# IOTM222.net
KiCad netlist of a schematic drawn in Altium Designer
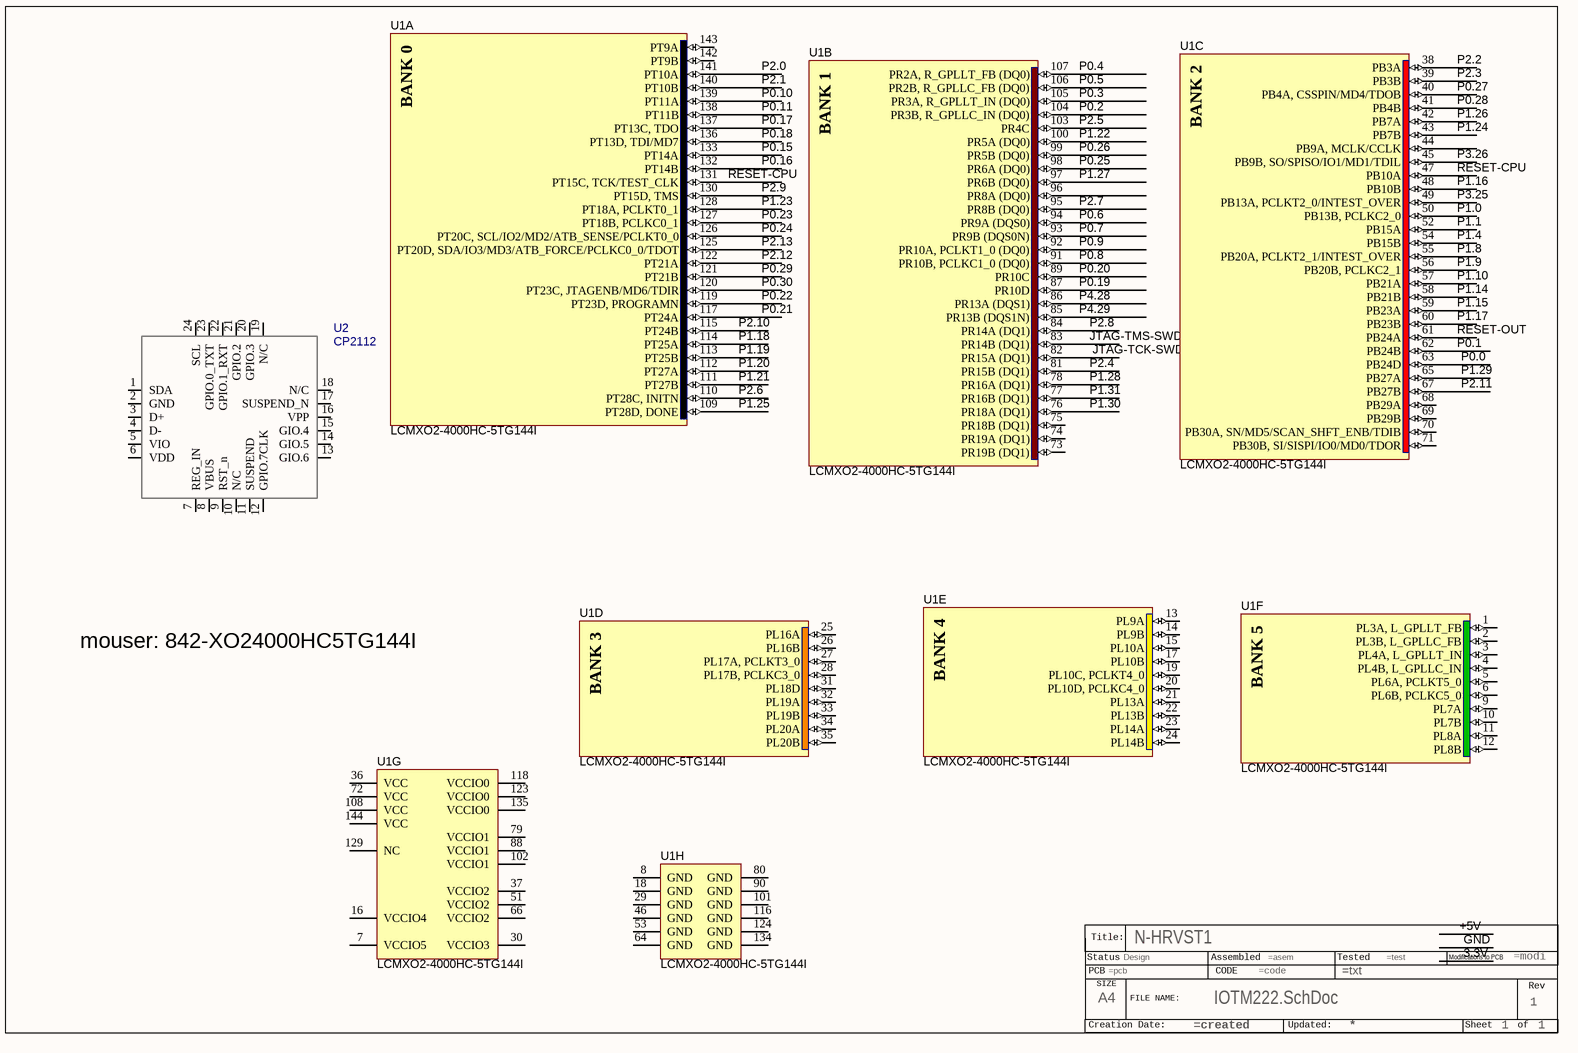
[diagram p0: IOTM222.SchDoc]

(export (version "E")
  (design (tool "Eeschema 10.0.6"))
  (components
    (comp (ref "?*")
      (value "TITLEBLOCK2")
      (fields (field (name "PAGE NUMPER") "1") (field (name "PAGE COUNT") "1"))
      (libsource (lib "NX2") (part "TITLEBLOCK2"))
    )
    (comp (ref "U1")
      (value "LCMXO2-4000HC-5TG144I")
      (footprint "TQFP144_N")
      (libsource (lib "MachXO2") (part "LCMXO2-4000HC-5TG144I"))
    )
    (comp (ref "U2") (value "CP2112") (footprint "QFN24") (libsource (lib "NX1") (part "CP2112")))
  )
  (nets
    (net (code "4") (name "/JTAG-TCK-SWDCLK") (class "Default")
      (node (ref "U1") (pin "82") (pinfunction "PR15A_(DQ1)_82") (pintype "bidirectional"))
    )
    (net (code "5") (name "/JTAG-TMS-SWDIO") (class "Default")
      (node (ref "U1") (pin "83") (pinfunction "PR14B_(DQ1)_83") (pintype "bidirectional"))
    )
    (net (code "6") (name "/P0.0") (class "Default")
      (node (ref "U1") (pin "63") (pinfunction "PB24D_63") (pintype "bidirectional"))
    )
    (net (code "7") (name "/P0.1") (class "Default")
      (node (ref "U1") (pin "62") (pinfunction "PB24B_62") (pintype "bidirectional"))
    )
    (net (code "8") (name "/P0.2") (class "Default")
      (node (ref "U1") (pin "104") (pinfunction "PR3B,_R_GPLLC_IN_(DQ0)_104") (pintype "bidirectional"))
    )
    (net (code "9") (name "/P0.3") (class "Default")
      (node (ref "U1") (pin "105") (pinfunction "PR3A,_R_GPLLT_IN_(DQ0)_105") (pintype "bidirectional"))
    )
    (net (code "10") (name "/P0.4") (class "Default")
      (node (ref "U1") (pin "107") (pinfunction "PR2A,_R_GPLLT_FB_(DQ0)_107") (pintype "bidirectional"))
    )
    (net (code "11") (name "/P0.5") (class "Default")
      (node (ref "U1") (pin "106") (pinfunction "PR2B,_R_GPLLC_FB_(DQ0)_106") (pintype "bidirectional"))
    )
    (net (code "12") (name "/P0.6") (class "Default")
      (node (ref "U1") (pin "94") (pinfunction "PR9A_(DQS0)_94") (pintype "bidirectional"))
    )
    (net (code "13") (name "/P0.7") (class "Default")
      (node (ref "U1") (pin "93") (pinfunction "PR9B_(DQS0N)_93") (pintype "bidirectional"))
    )
    (net (code "14") (name "/P0.8") (class "Default")
      (node (ref "U1") (pin "91") (pinfunction "PR10B,_PCLKC1_0_(DQ0)_91") (pintype "bidirectional"))
    )
    (net (code "15") (name "/P0.9") (class "Default")
      (node (ref "U1") (pin "92") (pinfunction "PR10A,_PCLKT1_0_(DQ0)_92") (pintype "bidirectional"))
    )
    (net (code "16") (name "/P0.10") (class "Default")
      (node (ref "U1") (pin "139") (pinfunction "PT11A_139") (pintype "bidirectional"))
    )
    (net (code "17") (name "/P0.11") (class "Default")
      (node (ref "U1") (pin "138") (pinfunction "PT11B_138") (pintype "bidirectional"))
    )
    (net (code "18") (name "/P0.15") (class "Default")
      (node (ref "U1") (pin "133") (pinfunction "PT14A_133") (pintype "bidirectional"))
    )
    (net (code "19") (name "/P0.16") (class "Default")
      (node (ref "U1") (pin "132") (pinfunction "PT14B_132") (pintype "bidirectional"))
    )
    (net (code "20") (name "/P0.17") (class "Default")
      (node (ref "U1") (pin "137") (pinfunction "PT13C,_TDO_137") (pintype "bidirectional"))
    )
    (net (code "21") (name "/P0.18") (class "Default")
      (node (ref "U1") (pin "136") (pinfunction "PT13D,_TDI/MD7_136") (pintype "bidirectional"))
    )
    (net (code "22") (name "/P0.19") (class "Default")
      (node (ref "U1") (pin "87") (pinfunction "PR10D_87") (pintype "bidirectional"))
    )
    (net (code "23") (name "/P0.20") (class "Default")
      (node (ref "U1") (pin "89") (pinfunction "PR10C_89") (pintype "bidirectional"))
    )
    (net (code "24") (name "/P0.21") (class "Default")
      (node (ref "U1") (pin "117") (pinfunction "PT24A_117") (pintype "bidirectional"))
    )
    (net (code "25") (name "/P0.22") (class "Default")
      (node (ref "U1") (pin "119") (pinfunction "PT23D,_PROGRAMN_119") (pintype "bidirectional"))
    )
    (net (code "26") (name "/P0.23") (class "Default")
      (node (ref "U1") (pin "127") (pinfunction "PT18B,_PCLKC0_1_127") (pintype "bidirectional"))
    )
    (net (code "27") (name "/P0.24") (class "Default")
      (node (ref "U1") (pin "126") (pinfunction "PT20C,_SCL/IO2/MD2/ATB_SENSE/PCLKT0_0_126") (pintype "bidirectional"))
    )
    (net (code "28") (name "/P0.25") (class "Default")
      (node (ref "U1") (pin "98") (pinfunction "PR6A_(DQ0)_98") (pintype "bidirectional"))
    )
    (net (code "29") (name "/P0.26") (class "Default")
      (node (ref "U1") (pin "99") (pinfunction "PR5B_(DQ0)_99") (pintype "bidirectional"))
    )
    (net (code "30") (name "/P0.27") (class "Default")
      (node (ref "U1") (pin "40") (pinfunction "PB4A,_CSSPIN/MD4/TDOB_40") (pintype "bidirectional"))
    )
    (net (code "31") (name "/P0.28") (class "Default")
      (node (ref "U1") (pin "41") (pinfunction "PB4B_41") (pintype "bidirectional"))
    )
    (net (code "32") (name "/P0.29") (class "Default")
      (node (ref "U1") (pin "121") (pinfunction "PT21B_121") (pintype "bidirectional"))
    )
    (net (code "33") (name "/P0.30") (class "Default")
      (node (ref "U1") (pin "120") (pinfunction "PT23C,_JTAGENB/MD6/TDIR_120") (pintype "bidirectional"))
    )
    (net (code "34") (name "/P1.0") (class "Default")
      (node (ref "U1") (pin "50") (pinfunction "PB13B,_PCLKC2_0_50") (pintype "bidirectional"))
    )
    (net (code "35") (name "/P1.1") (class "Default")
      (node (ref "U1") (pin "52") (pinfunction "PB15A_52") (pintype "bidirectional"))
    )
    (net (code "36") (name "/P1.4") (class "Default")
      (node (ref "U1") (pin "54") (pinfunction "PB15B_54") (pintype "bidirectional"))
    )
    (net (code "37") (name "/P1.8") (class "Default")
      (node (ref "U1") (pin "55") (pinfunction "PB20A,_PCLKT2_1/INTEST_OVER_55") (pintype "bidirectional"))
    )
    (net (code "38") (name "/P1.9") (class "Default")
      (node (ref "U1") (pin "56") (pinfunction "PB20B,_PCLKC2_1_56") (pintype "bidirectional"))
    )
    (net (code "39") (name "/P1.10") (class "Default")
      (node (ref "U1") (pin "57") (pinfunction "PB21A_57") (pintype "bidirectional"))
    )
    (net (code "40") (name "/P1.14") (class "Default")
      (node (ref "U1") (pin "58") (pinfunction "PB21B_58") (pintype "bidirectional"))
    )
    (net (code "41") (name "/P1.15") (class "Default")
      (node (ref "U1") (pin "59") (pinfunction "PB23A_59") (pintype "bidirectional"))
    )
    (net (code "42") (name "/P1.16") (class "Default")
      (node (ref "U1") (pin "48") (pinfunction "PB10B_48") (pintype "bidirectional"))
    )
    (net (code "43") (name "/P1.17") (class "Default")
      (node (ref "U1") (pin "60") (pinfunction "PB23B_60") (pintype "bidirectional"))
    )
    (net (code "44") (name "/P1.18") (class "Default")
      (node (ref "U1") (pin "114") (pinfunction "PT25A_114") (pintype "bidirectional"))
    )
    (net (code "45") (name "/P1.19") (class "Default")
      (node (ref "U1") (pin "113") (pinfunction "PT25B_113") (pintype "bidirectional"))
    )
    (net (code "46") (name "/P1.20") (class "Default")
      (node (ref "U1") (pin "112") (pinfunction "PT27A_112") (pintype "bidirectional"))
    )
    (net (code "47") (name "/P1.21") (class "Default")
      (node (ref "U1") (pin "111") (pinfunction "PT27B_111") (pintype "bidirectional"))
    )
    (net (code "48") (name "/P1.22") (class "Default")
      (node (ref "U1") (pin "100") (pinfunction "PR5A_(DQ0)_100") (pintype "bidirectional"))
    )
    (net (code "49") (name "/P1.23") (class "Default")
      (node (ref "U1") (pin "128") (pinfunction "PT18A,_PCLKT0_1_128") (pintype "bidirectional"))
    )
    (net (code "50") (name "/P1.24") (class "Default")
      (node (ref "U1") (pin "43") (pinfunction "PB7B_43") (pintype "bidirectional"))
    )
    (net (code "51") (name "/P1.25") (class "Default")
      (node (ref "U1") (pin "109") (pinfunction "PT28D,_DONE_109") (pintype "bidirectional"))
    )
    (net (code "52") (name "/P1.26") (class "Default")
      (node (ref "U1") (pin "42") (pinfunction "PB7A_42") (pintype "bidirectional"))
    )
    (net (code "53") (name "/P1.27") (class "Default")
      (node (ref "U1") (pin "97") (pinfunction "PR6B_(DQ0)_97") (pintype "bidirectional"))
    )
    (net (code "54") (name "/P1.28") (class "Default")
      (node (ref "U1") (pin "78") (pinfunction "PR16A_(DQ1)_78") (pintype "bidirectional"))
    )
    (net (code "55") (name "/P1.29") (class "Default")
      (node (ref "U1") (pin "65") (pinfunction "PB27A_65") (pintype "bidirectional"))
    )
    (net (code "56") (name "/P1.30") (class "Default")
      (node (ref "U1") (pin "76") (pinfunction "PR18A_(DQ1)_76") (pintype "bidirectional"))
    )
    (net (code "57") (name "/P1.31") (class "Default")
      (node (ref "U1") (pin "77") (pinfunction "PR16B_(DQ1)_77") (pintype "bidirectional"))
    )
    (net (code "58") (name "/P2.0") (class "Default")
      (node (ref "U1") (pin "141") (pinfunction "PT10A_141") (pintype "bidirectional"))
    )
    (net (code "59") (name "/P2.1") (class "Default")
      (node (ref "U1") (pin "140") (pinfunction "PT10B_140") (pintype "bidirectional"))
    )
    (net (code "60") (name "/P2.2") (class "Default")
      (node (ref "U1") (pin "38") (pinfunction "PB3A_38") (pintype "bidirectional"))
    )
    (net (code "61") (name "/P2.3") (class "Default")
      (node (ref "U1") (pin "39") (pinfunction "PB3B_39") (pintype "bidirectional"))
    )
    (net (code "62") (name "/P2.4") (class "Default")
      (node (ref "U1") (pin "81") (pinfunction "PR15B_(DQ1)_81") (pintype "bidirectional"))
    )
    (net (code "63") (name "/P2.5") (class "Default")
      (node (ref "U1") (pin "103") (pinfunction "PR4C_103") (pintype "bidirectional"))
    )
    (net (code "64") (name "/P2.6") (class "Default")
      (node (ref "U1") (pin "110") (pinfunction "PT28C,_INITN_110") (pintype "bidirectional"))
    )
    (net (code "65") (name "/P2.7") (class "Default")
      (node (ref "U1") (pin "95") (pinfunction "PR8B_(DQ0)_95") (pintype "bidirectional"))
    )
    (net (code "66") (name "/P2.8") (class "Default")
      (node (ref "U1") (pin "84") (pinfunction "PR14A_(DQ1)_84") (pintype "bidirectional"))
    )
    (net (code "67") (name "/P2.9") (class "Default")
      (node (ref "U1") (pin "130") (pinfunction "PT15D,_TMS_130") (pintype "bidirectional"))
    )
    (net (code "68") (name "/P2.10") (class "Default")
      (node (ref "U1") (pin "115") (pinfunction "PT24B_115") (pintype "bidirectional"))
    )
    (net (code "69") (name "/P2.11") (class "Default")
      (node (ref "U1") (pin "67") (pinfunction "PB27B_67") (pintype "bidirectional"))
    )
    (net (code "70") (name "/P2.12") (class "Default")
      (node (ref "U1") (pin "122") (pinfunction "PT21A_122") (pintype "bidirectional"))
    )
    (net (code "71") (name "/P2.13") (class "Default")
      (node (ref "U1") (pin "125") (pinfunction "PT20D,_SDA/IO3/MD3/ATB_FORCE/PCLKC0_0/TDOT_125") (pintype "bidirectional"))
    )
    (net (code "72") (name "/P3.25") (class "Default")
      (node (ref "U1") (pin "49") (pinfunction "PB13A,_PCLKT2_0/INTEST_OVER_49") (pintype "bidirectional"))
    )
    (net (code "73") (name "/P3.26") (class "Default")
      (node (ref "U1") (pin "45") (pinfunction "PB9B,_SO/SPISO/IO1/MD1/TDIL_45") (pintype "bidirectional"))
    )
    (net (code "74") (name "/P4.28") (class "Default")
      (node (ref "U1") (pin "86") (pinfunction "PR13A_(DQS1)_86") (pintype "bidirectional"))
    )
    (net (code "75") (name "/P4.29") (class "Default")
      (node (ref "U1") (pin "85") (pinfunction "PR13B_(DQS1N)_85") (pintype "bidirectional"))
    )
    (net (code "76") (name "/RESET-CPU") (class "Default")
      (node (ref "U1") (pin "131") (pinfunction "PT15C,_TCK/TEST_CLK_131") (pintype "bidirectional"))
      (node (ref "U1") (pin "47") (pinfunction "PB10A_47") (pintype "bidirectional"))
    )
    (net (code "77") (name "/RESET-OUT") (class "Default")
      (node (ref "U1") (pin "61") (pinfunction "PB24A_61") (pintype "bidirectional"))
    )
    (net (code "78") (name "unconnected-(?*-Pad)") (class "Default")
      (node (ref "?*") (pin "") (pintype "passive"))
    )
    (net (code "79") (name "unconnected-(U1A-PT9A-Pad143)") (class "Default")
      (node (ref "U1") (pin "143") (pinfunction "PT9A_143") (pintype "bidirectional"))
    )
    (net (code "80") (name "unconnected-(U1A-PT9B-Pad142)") (class "Default")
      (node (ref "U1") (pin "142") (pinfunction "PT9B_142") (pintype "bidirectional"))
    )
    (net (code "81") (name "unconnected-(U1B-PR8A_(DQ0)-Pad96)") (class "Default")
      (node (ref "U1") (pin "96") (pinfunction "PR8A_(DQ0)_96") (pintype "bidirectional"))
    )
    (net (code "82") (name "unconnected-(U1B-PR18B_(DQ1)-Pad75)") (class "Default")
      (node (ref "U1") (pin "75") (pinfunction "PR18B_(DQ1)_75") (pintype "bidirectional"))
    )
    (net (code "83") (name "unconnected-(U1B-PR19A_(DQ1)-Pad74)") (class "Default")
      (node (ref "U1") (pin "74") (pinfunction "PR19A_(DQ1)_74") (pintype "bidirectional"))
    )
    (net (code "84") (name "unconnected-(U1B-PR19B_(DQ1)-Pad73)") (class "Default")
      (node (ref "U1") (pin "73") (pinfunction "PR19B_(DQ1)_73") (pintype "bidirectional"))
    )
    (net (code "85") (name "unconnected-(U1C-PB9A,_MCLK{slash}CCLK-Pad44)") (class "Default")
      (node (ref "U1") (pin "44") (pinfunction "PB9A,_MCLK/CCLK_44") (pintype "bidirectional"))
    )
    (net (code "86") (name "unconnected-(U1C-PB29A-Pad68)") (class "Default")
      (node (ref "U1") (pin "68") (pinfunction "PB29A_68") (pintype "bidirectional"))
    )
    (net (code "87") (name "unconnected-(U1C-PB29B-Pad69)") (class "Default")
      (node (ref "U1") (pin "69") (pinfunction "PB29B_69") (pintype "bidirectional"))
    )
    (net (code "88") (name "unconnected-(U1C-PB30A,_SN{slash}MD5{slash}SCAN_SHFT_ENB{slash}TDIB-Pad70)") (class "Default")
      (node (ref "U1") (pin "70") (pinfunction "PB30A,_SN/MD5/SCAN_SHFT_ENB/TDIB_70") (pintype "bidirectional"))
    )
    (net (code "89") (name "unconnected-(U1C-PB30B,_SI{slash}SISPI{slash}IO0{slash}MD0{slash}TDOR-Pad71)") (class "Default")
      (node (ref "U1") (pin "71") (pinfunction "PB30B,_SI/SISPI/IO0/MD0/TDOR_71") (pintype "bidirectional"))
    )
    (net (code "90") (name "unconnected-(U1D-PL16A-Pad25)") (class "Default")
      (node (ref "U1") (pin "25") (pinfunction "PL16A_25") (pintype "bidirectional"))
    )
    (net (code "91") (name "unconnected-(U1D-PL16B-Pad26)") (class "Default")
      (node (ref "U1") (pin "26") (pinfunction "PL16B_26") (pintype "bidirectional"))
    )
    (net (code "92") (name "unconnected-(U1D-PL17A,_PCLKT3_0-Pad27)") (class "Default")
      (node (ref "U1") (pin "27") (pinfunction "PL17A,_PCLKT3_0_27") (pintype "bidirectional"))
    )
    (net (code "93") (name "unconnected-(U1D-PL17B,_PCLKC3_0-Pad28)") (class "Default")
      (node (ref "U1") (pin "28") (pinfunction "PL17B,_PCLKC3_0_28") (pintype "bidirectional"))
    )
    (net (code "94") (name "unconnected-(U1D-PL18D-Pad31)") (class "Default")
      (node (ref "U1") (pin "31") (pinfunction "PL18D_31") (pintype "bidirectional"))
    )
    (net (code "95") (name "unconnected-(U1D-PL19A-Pad32)") (class "Default")
      (node (ref "U1") (pin "32") (pinfunction "PL19A_32") (pintype "bidirectional"))
    )
    (net (code "96") (name "unconnected-(U1D-PL19B-Pad33)") (class "Default")
      (node (ref "U1") (pin "33") (pinfunction "PL19B_33") (pintype "bidirectional"))
    )
    (net (code "97") (name "unconnected-(U1D-PL20A-Pad34)") (class "Default")
      (node (ref "U1") (pin "34") (pinfunction "PL20A_34") (pintype "bidirectional"))
    )
    (net (code "98") (name "unconnected-(U1D-PL20B-Pad35)") (class "Default")
      (node (ref "U1") (pin "35") (pinfunction "PL20B_35") (pintype "bidirectional"))
    )
    (net (code "99") (name "unconnected-(U1E-PL9A-Pad13)") (class "Default")
      (node (ref "U1") (pin "13") (pinfunction "PL9A_13") (pintype "bidirectional"))
    )
    (net (code "100") (name "unconnected-(U1E-PL9B-Pad14)") (class "Default")
      (node (ref "U1") (pin "14") (pinfunction "PL9B_14") (pintype "bidirectional"))
    )
    (net (code "101") (name "unconnected-(U1E-PL10A-Pad15)") (class "Default")
      (node (ref "U1") (pin "15") (pinfunction "PL10A_15") (pintype "bidirectional"))
    )
    (net (code "102") (name "unconnected-(U1E-PL10B-Pad17)") (class "Default")
      (node (ref "U1") (pin "17") (pinfunction "PL10B_17") (pintype "bidirectional"))
    )
    (net (code "103") (name "unconnected-(U1E-PL10C,_PCLKT4_0-Pad19)") (class "Default")
      (node (ref "U1") (pin "19") (pinfunction "PL10C,_PCLKT4_0_19") (pintype "bidirectional"))
    )
    (net (code "104") (name "unconnected-(U1E-PL10D,_PCLKC4_0-Pad20)") (class "Default")
      (node (ref "U1") (pin "20") (pinfunction "PL10D,_PCLKC4_0_20") (pintype "bidirectional"))
    )
    (net (code "105") (name "unconnected-(U1E-PL13A-Pad21)") (class "Default")
      (node (ref "U1") (pin "21") (pinfunction "PL13A_21") (pintype "bidirectional"))
    )
    (net (code "106") (name "unconnected-(U1E-PL13B-Pad22)") (class "Default")
      (node (ref "U1") (pin "22") (pinfunction "PL13B_22") (pintype "bidirectional"))
    )
    (net (code "107") (name "unconnected-(U1E-PL14A-Pad23)") (class "Default")
      (node (ref "U1") (pin "23") (pinfunction "PL14A_23") (pintype "bidirectional"))
    )
    (net (code "108") (name "unconnected-(U1E-PL14B-Pad24)") (class "Default")
      (node (ref "U1") (pin "24") (pinfunction "PL14B_24") (pintype "bidirectional"))
    )
    (net (code "109") (name "unconnected-(U1F-PL3A,_L_GPLLT_FB-Pad1)") (class "Default")
      (node (ref "U1") (pin "1") (pinfunction "PL3A,_L_GPLLT_FB_1") (pintype "bidirectional"))
    )
    (net (code "110") (name "unconnected-(U1F-PL3B,_L_GPLLC_FB-Pad2)") (class "Default")
      (node (ref "U1") (pin "2") (pinfunction "PL3B,_L_GPLLC_FB_2") (pintype "bidirectional"))
    )
    (net (code "111") (name "unconnected-(U1F-PL4A,_L_GPLLT_IN-Pad3)") (class "Default")
      (node (ref "U1") (pin "3") (pinfunction "PL4A,_L_GPLLT_IN_3") (pintype "bidirectional"))
    )
    (net (code "112") (name "unconnected-(U1F-PL4B,_L_GPLLC_IN-Pad4)") (class "Default")
      (node (ref "U1") (pin "4") (pinfunction "PL4B,_L_GPLLC_IN_4") (pintype "bidirectional"))
    )
    (net (code "113") (name "unconnected-(U1F-PL6A,_PCLKT5_0-Pad5)") (class "Default")
      (node (ref "U1") (pin "5") (pinfunction "PL6A,_PCLKT5_0_5") (pintype "bidirectional"))
    )
    (net (code "114") (name "unconnected-(U1F-PL6B,_PCLKC5_0-Pad6)") (class "Default")
      (node (ref "U1") (pin "6") (pinfunction "PL6B,_PCLKC5_0_6") (pintype "bidirectional"))
    )
    (net (code "115") (name "unconnected-(U1F-PL7A-Pad9)") (class "Default")
      (node (ref "U1") (pin "9") (pinfunction "PL7A_9") (pintype "bidirectional"))
    )
    (net (code "116") (name "unconnected-(U1F-PL7B-Pad10)") (class "Default")
      (node (ref "U1") (pin "10") (pinfunction "PL7B_10") (pintype "bidirectional"))
    )
    (net (code "117") (name "unconnected-(U1F-PL8A-Pad11)") (class "Default")
      (node (ref "U1") (pin "11") (pinfunction "PL8A_11") (pintype "bidirectional"))
    )
    (net (code "118") (name "unconnected-(U1F-PL8B-Pad12)") (class "Default")
      (node (ref "U1") (pin "12") (pinfunction "PL8B_12") (pintype "bidirectional"))
    )
    (net (code "119") (name "unconnected-(U1G-NC-Pad129)") (class "Default")
      (node (ref "U1") (pin "129") (pinfunction "NC_129") (pintype "passive"))
    )
    (net (code "120") (name "unconnected-(U1G-VCC-Pad36)") (class "Default")
      (node (ref "U1") (pin "36") (pinfunction "VCC_36") (pintype "power_in"))
    )
    (net (code "121") (name "unconnected-(U1G-VCC-Pad72)") (class "Default")
      (node (ref "U1") (pin "72") (pinfunction "VCC_72") (pintype "power_in"))
    )
    (net (code "122") (name "unconnected-(U1G-VCC-Pad108)") (class "Default")
      (node (ref "U1") (pin "108") (pinfunction "VCC_108") (pintype "power_in"))
    )
    (net (code "123") (name "unconnected-(U1G-VCC-Pad144)") (class "Default")
      (node (ref "U1") (pin "144") (pinfunction "VCC_144") (pintype "power_in"))
    )
    (net (code "124") (name "unconnected-(U1G-VCCIO0-Pad118)") (class "Default")
      (node (ref "U1") (pin "118") (pinfunction "VCCIO0_118") (pintype "power_in"))
    )
    (net (code "125") (name "unconnected-(U1G-VCCIO0-Pad123)") (class "Default")
      (node (ref "U1") (pin "123") (pinfunction "VCCIO0_123") (pintype "power_in"))
    )
    (net (code "126") (name "unconnected-(U1G-VCCIO0-Pad135)") (class "Default")
      (node (ref "U1") (pin "135") (pinfunction "VCCIO0_135") (pintype "power_in"))
    )
    (net (code "127") (name "unconnected-(U1G-VCCIO1-Pad79)") (class "Default")
      (node (ref "U1") (pin "79") (pinfunction "VCCIO1_79") (pintype "power_in"))
    )
    (net (code "128") (name "unconnected-(U1G-VCCIO1-Pad88)") (class "Default")
      (node (ref "U1") (pin "88") (pinfunction "VCCIO1_88") (pintype "power_in"))
    )
    (net (code "129") (name "unconnected-(U1G-VCCIO1-Pad102)") (class "Default")
      (node (ref "U1") (pin "102") (pinfunction "VCCIO1_102") (pintype "power_in"))
    )
    (net (code "130") (name "unconnected-(U1G-VCCIO2-Pad37)") (class "Default")
      (node (ref "U1") (pin "37") (pinfunction "VCCIO2_37") (pintype "power_in"))
    )
    (net (code "131") (name "unconnected-(U1G-VCCIO2-Pad51)") (class "Default")
      (node (ref "U1") (pin "51") (pinfunction "VCCIO2_51") (pintype "power_in"))
    )
    (net (code "132") (name "unconnected-(U1G-VCCIO2-Pad66)") (class "Default")
      (node (ref "U1") (pin "66") (pinfunction "VCCIO2_66") (pintype "power_in"))
    )
    (net (code "133") (name "unconnected-(U1G-VCCIO3-Pad30)") (class "Default")
      (node (ref "U1") (pin "30") (pinfunction "VCCIO3_30") (pintype "power_in"))
    )
    (net (code "134") (name "unconnected-(U1G-VCCIO4-Pad16)") (class "Default")
      (node (ref "U1") (pin "16") (pinfunction "VCCIO4_16") (pintype "power_in"))
    )
    (net (code "135") (name "unconnected-(U1G-VCCIO5-Pad7)") (class "Default")
      (node (ref "U1") (pin "7") (pinfunction "VCCIO5_7") (pintype "power_in"))
    )
    (net (code "136") (name "unconnected-(U1H-GND-Pad8)") (class "Default")
      (node (ref "U1") (pin "8") (pinfunction "GND_8") (pintype "power_in"))
    )
    (net (code "137") (name "unconnected-(U1H-GND-Pad18)") (class "Default")
      (node (ref "U1") (pin "18") (pinfunction "GND_18") (pintype "power_in"))
    )
    (net (code "138") (name "unconnected-(U1H-GND-Pad29)") (class "Default")
      (node (ref "U1") (pin "29") (pinfunction "GND_29") (pintype "power_in"))
    )
    (net (code "139") (name "unconnected-(U1H-GND-Pad46)") (class "Default")
      (node (ref "U1") (pin "46") (pinfunction "GND_46") (pintype "power_in"))
    )
    (net (code "140") (name "unconnected-(U1H-GND-Pad53)") (class "Default")
      (node (ref "U1") (pin "53") (pinfunction "GND_53") (pintype "power_in"))
    )
    (net (code "141") (name "unconnected-(U1H-GND-Pad64)") (class "Default")
      (node (ref "U1") (pin "64") (pinfunction "GND_64") (pintype "power_in"))
    )
    (net (code "142") (name "unconnected-(U1H-GND-Pad80)") (class "Default")
      (node (ref "U1") (pin "80") (pinfunction "GND_80") (pintype "power_in"))
    )
    (net (code "143") (name "unconnected-(U1H-GND-Pad90)") (class "Default")
      (node (ref "U1") (pin "90") (pinfunction "GND_90") (pintype "power_in"))
    )
    (net (code "144") (name "unconnected-(U1H-GND-Pad101)") (class "Default")
      (node (ref "U1") (pin "101") (pinfunction "GND_101") (pintype "power_in"))
    )
    (net (code "145") (name "unconnected-(U1H-GND-Pad116)") (class "Default")
      (node (ref "U1") (pin "116") (pinfunction "GND_116") (pintype "power_in"))
    )
    (net (code "146") (name "unconnected-(U1H-GND-Pad124)") (class "Default")
      (node (ref "U1") (pin "124") (pinfunction "GND_124") (pintype "power_in"))
    )
    (net (code "147") (name "unconnected-(U1H-GND-Pad134)") (class "Default")
      (node (ref "U1") (pin "134") (pinfunction "GND_134") (pintype "power_in"))
    )
    (net (code "148") (name "unconnected-(U2-D+-Pad3)") (class "Default")
      (node (ref "U2") (pin "3") (pinfunction "D+_3") (pintype "passive"))
    )
    (net (code "149") (name "unconnected-(U2-D--Pad4)") (class "Default")
      (node (ref "U2") (pin "4") (pinfunction "D-_4") (pintype "passive"))
    )
    (net (code "150") (name "unconnected-(U2-GIO.4-Pad15)") (class "Default")
      (node (ref "U2") (pin "15") (pinfunction "GIO.4_15") (pintype "passive"))
    )
    (net (code "151") (name "unconnected-(U2-GIO.5-Pad14)") (class "Default")
      (node (ref "U2") (pin "14") (pinfunction "GIO.5_14") (pintype "passive"))
    )
    (net (code "152") (name "unconnected-(U2-GIO.6-Pad13)") (class "Default")
      (node (ref "U2") (pin "13") (pinfunction "GIO.6_13") (pintype "passive"))
    )
    (net (code "153") (name "unconnected-(U2-GND-Pad2)") (class "Default")
      (node (ref "U2") (pin "2") (pinfunction "GND_2") (pintype "passive"))
    )
    (net (code "154") (name "unconnected-(U2-GPIO.0_TXT-Pad23)") (class "Default")
      (node (ref "U2") (pin "23") (pinfunction "GPIO.0_TXT_23") (pintype "passive"))
    )
    (net (code "155") (name "unconnected-(U2-GPIO.1_RXT-Pad22)") (class "Default")
      (node (ref "U2") (pin "22") (pinfunction "GPIO.1_RXT_22") (pintype "passive"))
    )
    (net (code "156") (name "unconnected-(U2-GPIO.2-Pad21)") (class "Default")
      (node (ref "U2") (pin "21") (pinfunction "GPIO.2_21") (pintype "passive"))
    )
    (net (code "157") (name "unconnected-(U2-GPIO.3-Pad20)") (class "Default")
      (node (ref "U2") (pin "20") (pinfunction "GPIO.3_20") (pintype "passive"))
    )
    (net (code "158") (name "unconnected-(U2-GPIO.7CLK-Pad12)") (class "Default")
      (node (ref "U2") (pin "12") (pinfunction "GPIO.7CLK_12") (pintype "passive"))
    )
    (net (code "159") (name "unconnected-(U2-N{slash}C-Pad10)") (class "Default")
      (node (ref "U2") (pin "10") (pinfunction "N/C_10") (pintype "passive"))
    )
    (net (code "160") (name "unconnected-(U2-N{slash}C-Pad18)") (class "Default")
      (node (ref "U2") (pin "18") (pinfunction "N/C_18") (pintype "passive"))
    )
    (net (code "161") (name "unconnected-(U2-N{slash}C-Pad19)") (class "Default")
      (node (ref "U2") (pin "19") (pinfunction "N/C_19") (pintype "passive"))
    )
    (net (code "162") (name "unconnected-(U2-REG_IN-Pad7)") (class "Default")
      (node (ref "U2") (pin "7") (pinfunction "REG_IN_7") (pintype "passive"))
    )
    (net (code "163") (name "unconnected-(U2-RST_n-Pad9)") (class "Default")
      (node (ref "U2") (pin "9") (pinfunction "RST_n_9") (pintype "passive"))
    )
    (net (code "164") (name "unconnected-(U2-SCL-Pad24)") (class "Default")
      (node (ref "U2") (pin "24") (pinfunction "SCL_24") (pintype "passive"))
    )
    (net (code "165") (name "unconnected-(U2-SDA-Pad1)") (class "Default")
      (node (ref "U2") (pin "1") (pinfunction "SDA_1") (pintype "passive"))
    )
    (net (code "166") (name "unconnected-(U2-SUSPEND-Pad11)") (class "Default")
      (node (ref "U2") (pin "11") (pinfunction "SUSPEND_11") (pintype "passive"))
    )
    (net (code "167") (name "unconnected-(U2-SUSPEND_N-Pad17)") (class "Default")
      (node (ref "U2") (pin "17") (pinfunction "SUSPEND_N_17") (pintype "passive"))
    )
    (net (code "168") (name "unconnected-(U2-VBUS-Pad8)") (class "Default")
      (node (ref "U2") (pin "8") (pinfunction "VBUS_8") (pintype "passive"))
    )
    (net (code "169") (name "unconnected-(U2-VDD-Pad6)") (class "Default")
      (node (ref "U2") (pin "6") (pinfunction "VDD_6") (pintype "passive"))
    )
    (net (code "170") (name "unconnected-(U2-VIO-Pad5)") (class "Default")
      (node (ref "U2") (pin "5") (pinfunction "VIO_5") (pintype "passive"))
    )
    (net (code "171") (name "unconnected-(U2-VPP-Pad16)") (class "Default")
      (node (ref "U2") (pin "16") (pinfunction "VPP_16") (pintype "passive"))
    )
  )
)
